# Optosense.net
KiCad netlist of a schematic drawn in Altium Designer
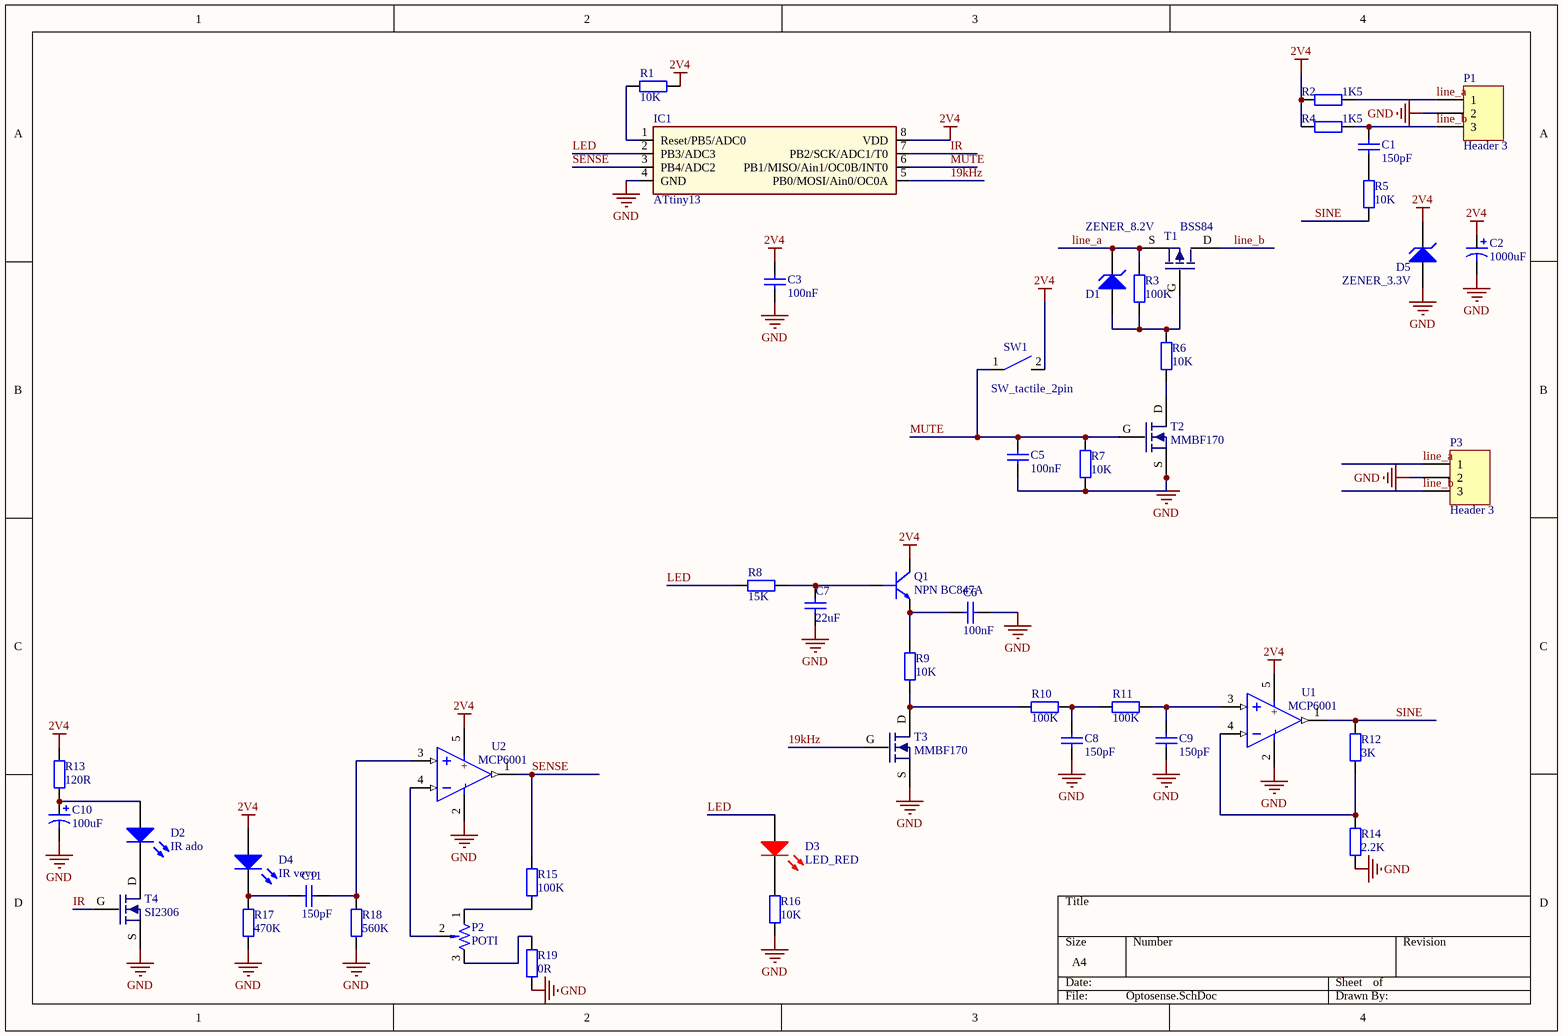
[diagram p0: Optosense.SchDoc]

(export (version "E")
  (design (tool "Eeschema 10.0.6"))
  (components
    (comp (ref "C1")
      (value "150pF")
      (footprint "FP_0603_CAP_080")
      (description "Capacitor")
      (libsource (lib "Capacitor") (part "CAP"))
    )
    (comp (ref "C2")
      (value "1000uF")
      (footprint "CAP_8x11_fekvo")
      (description "Polarized Capacitor")
      (libsource (lib "Capacitor") (part "CAP_ELECT"))
    )
    (comp (ref "C3")
      (value "100nF")
      (footprint "FP_0603_CAP_080")
      (description "Capacitor")
      (libsource (lib "Capacitor") (part "CAP"))
    )
    (comp (ref "C5")
      (value "100nF")
      (footprint "FP_0603_CAP_080")
      (description "Capacitor")
      (libsource (lib "Capacitor") (part "CAP"))
    )
    (comp (ref "C6")
      (value "100nF")
      (footprint "FP_0603_CAP_080")
      (description "Capacitor")
      (libsource (lib "Capacitor") (part "CAP"))
    )
    (comp (ref "C7")
      (value "22uF")
      (footprint "FP_1206_CAP_125")
      (description "Capacitor")
      (libsource (lib "Miscellaneous Devices") (part "Cap"))
    )
    (comp (ref "C8")
      (value "150pF")
      (footprint "FP_0603_CAP_080")
      (description "Capacitor")
      (libsource (lib "Capacitor") (part "CAP"))
    )
    (comp (ref "C9")
      (value "150pF")
      (footprint "FP_0603_CAP_080")
      (description "Capacitor")
      (libsource (lib "Capacitor") (part "CAP"))
    )
    (comp (ref "C10")
      (value "100uF")
      (footprint "FP_3528")
      (description "Polarized Capacitor")
      (libsource (lib "Capacitor") (part "CAP_ELECT"))
    )
    (comp (ref "C11")
      (value "150pF")
      (footprint "FP_0603_CAP_080")
      (description "Capacitor")
      (libsource (lib "Capacitor") (part "CAP"))
    )
    (comp (ref "D1")
      (value "ZENER_8.2V")
      (footprint "SOD-80")
      (description "Zener Diode")
      (libsource (lib "Diode") (part "ZENER"))
    )
    (comp (ref "D2")
      (value "IR ado")
      (footprint "LED_IR_5mm")
      (description "Typical LED")
      (libsource (lib "Led_optical") (part "LED_B"))
    )
    (comp (ref "D3")
      (value "LED_RED")
      (footprint "led_3mm_standing R")
      (description "Typical LED")
      (libsource (lib "Led_optical") (part "LED_R"))
    )
    (comp (ref "D4")
      (value "IR vevo")
      (footprint "LED_IR_5mm")
      (description "Typical LED")
      (libsource (lib "Led_optical") (part "LED_B"))
    )
    (comp (ref "D5")
      (value "ZENER_3.3V")
      (footprint "SOD-80")
      (description "Zener Diode")
      (libsource (lib "Diode") (part "ZENER"))
    )
    (comp (ref "IC1") (value "ATtiny13") (footprint "WSON_n_SOIC8") (libsource (lib "uC") (part "ATtiny13")))
    (comp (ref "P1")
      (value "Header 3")
      (footprint "HDR1X3")
      (description "Header, 3-Pin")
      (fields (field (name "PUBLISHER") "Altium Limited"))
      (libsource (lib "Miscellaneous Connectors") (part "Header 3"))
    )
    (comp (ref "P2")
      (value "POTI")
      (footprint "RES_trimmer_helipot_mini_90")
      (libsource (lib "Resistor") (part "POTI"))
    )
    (comp (ref "P3")
      (value "Header 3")
      (footprint "HDR1X3")
      (description "Header, 3-Pin")
      (fields (field (name "PUBLISHER") "Altium Limited"))
      (libsource (lib "Miscellaneous Connectors") (part "Header 3"))
    )
    (comp (ref "Q1") (value "NPN BC847A") (footprint "TR_SOT23") (libsource (lib "Transistor") (part "NPN")))
    (comp (ref "R1")
      (value "10K")
      (footprint "FP_0603_RES")
      (description "Resistor")
      (libsource (lib "") (part "RES_1"))
    )
    (comp (ref "R2")
      (value "1K5")
      (footprint "FP_0603_RES")
      (description "Resistor")
      (libsource (lib "") (part "RES_3"))
    )
    (comp (ref "R3")
      (value "100K")
      (footprint "FP_0603_RES")
      (description "Resistor")
      (libsource (lib "Resistor") (part "RES"))
    )
    (comp (ref "R4")
      (value "1K5")
      (footprint "FP_0603_RES")
      (description "Resistor")
      (libsource (lib "") (part "RES_3"))
    )
    (comp (ref "R5")
      (value "10K")
      (footprint "FP_0603_RES")
      (description "Resistor")
      (libsource (lib "") (part "RES_2"))
    )
    (comp (ref "R6")
      (value "10K")
      (footprint "FP_0603_RES")
      (description "Resistor")
      (libsource (lib "Resistor") (part "RES"))
    )
    (comp (ref "R7")
      (value "10K")
      (footprint "FP_0603_RES")
      (description "Resistor")
      (libsource (lib "Resistor") (part "RES"))
    )
    (comp (ref "R8")
      (value "15K")
      (footprint "FP_0603_RES")
      (description "Resistor")
      (libsource (lib "") (part "RES_1"))
    )
    (comp (ref "R9")
      (value "10K")
      (footprint "FP_0603_RES")
      (description "Resistor")
      (libsource (lib "Resistor") (part "RES"))
    )
    (comp (ref "R10")
      (value "100K")
      (footprint "FP_0603_RES")
      (description "Resistor")
      (libsource (lib "") (part "RES_1"))
    )
    (comp (ref "R11")
      (value "100K")
      (footprint "FP_0603_RES")
      (description "Resistor")
      (libsource (lib "") (part "RES_1"))
    )
    (comp (ref "R12")
      (value "3K")
      (footprint "FP_0603_RES")
      (description "Resistor")
      (libsource (lib "Resistor") (part "RES"))
    )
    (comp (ref "R13")
      (value "120R")
      (footprint "FP_0603_RES")
      (description "Resistor")
      (libsource (lib "") (part "RES_2"))
    )
    (comp (ref "R14")
      (value "2.2K")
      (footprint "FP_0603_RES")
      (description "Resistor")
      (libsource (lib "Resistor") (part "RES"))
    )
    (comp (ref "R15")
      (value "100K")
      (footprint "FP_0603_RES")
      (description "Resistor")
      (libsource (lib "") (part "RES_2"))
    )
    (comp (ref "R16")
      (value "10K")
      (footprint "FP_0603_RES")
      (description "Resistor")
      (libsource (lib "") (part "RES_2"))
    )
    (comp (ref "R17")
      (value "470K")
      (footprint "FP_0603_RES")
      (description "Resistor")
      (libsource (lib "") (part "RES_2"))
    )
    (comp (ref "R18")
      (value "560K")
      (footprint "FP_0603_RES")
      (description "Resistor")
      (libsource (lib "") (part "RES_2"))
    )
    (comp (ref "R19")
      (value "0R")
      (footprint "FP_0603_RES")
      (description "Resistor")
      (libsource (lib "") (part "RES_2"))
    )
    (comp (ref "SW1")
      (value "SW_tactile_2pin")
      (footprint "SW_TACT_2PIN")
      (libsource (lib "Switch") (part "SW_tactile_2pin"))
    )
    (comp (ref "T1") (value "BSS84") (footprint "FET_SOT23") (libsource (lib "FET") (part "PMOS")))
    (comp (ref "T2") (value "MMBF170") (footprint "FET_SOT23") (libsource (lib "FET") (part "NMOS")))
    (comp (ref "T3") (value "MMBF170") (footprint "FET_SOT23") (libsource (lib "FET") (part "NMOS")))
    (comp (ref "T4") (value "SI2306") (footprint "FET_SOT23") (libsource (lib "FET") (part "NMOS")))
    (comp (ref "U1")
      (value "MCP6001")
      (footprint "ANALOG_SOT23-5")
      (libsource (lib "Analog") (part "MCP6001"))
    )
    (comp (ref "U2")
      (value "MCP6001")
      (footprint "ANALOG_SOT23-5")
      (libsource (lib "Analog") (part "MCP6001"))
    )
  )
  (nets
    (net (code "1") (name "/19kHz") (class "Default")
      (node (ref "IC1") (pin "5") (pinfunction "PB0/MOSI/Ain0/OC0A_5") (pintype "passive"))
      (node (ref "T3") (pin "G") (pinfunction "G_G") (pintype "passive"))
    )
    (net (code "2") (name "/IR") (class "Default")
      (node (ref "IC1") (pin "7") (pinfunction "PB2/SCK/ADC1/T0_7") (pintype "passive"))
      (node (ref "T4") (pin "G") (pinfunction "G_G") (pintype "passive"))
    )
    (net (code "3") (name "/LED") (class "Default")
      (node (ref "D3") (pin "A") (pinfunction "A_A") (pintype "passive"))
      (node (ref "IC1") (pin "2") (pinfunction "PB3/ADC3_2") (pintype "passive"))
      (node (ref "R8") (pin "2") (pinfunction "2_2") (pintype "passive"))
    )
    (net (code "4") (name "/MUTE") (class "Default")
      (node (ref "C5") (pin "2") (pinfunction "2_2") (pintype "passive"))
      (node (ref "IC1") (pin "6") (pinfunction "PB1/MISO/Ain1/OC0B/INT0_6") (pintype "passive"))
      (node (ref "R7") (pin "1") (pinfunction "1_1") (pintype "passive"))
      (node (ref "SW1") (pin "1") (pinfunction "1_1") (pintype "passive"))
      (node (ref "T2") (pin "G") (pinfunction "G_G") (pintype "passive"))
    )
    (net (code "5") (name "/SENSE") (class "Default")
      (node (ref "IC1") (pin "3") (pinfunction "PB4/ADC2_3") (pintype "passive"))
      (node (ref "R15") (pin "2") (pinfunction "2_2") (pintype "passive"))
      (node (ref "U2") (pin "1") (pinfunction "OUT1_1") (pintype "output"))
    )
    (net (code "6") (name "/SINE") (class "Default")
      (node (ref "R12") (pin "1") (pinfunction "1_1") (pintype "passive"))
      (node (ref "R5") (pin "1") (pinfunction "1_1") (pintype "passive"))
      (node (ref "U1") (pin "1") (pinfunction "OUT1_1") (pintype "output"))
    )
    (net (code "7") (name "/line_a") (class "Default")
      (node (ref "D1") (pin "K") (pinfunction "K_K") (pintype "passive"))
      (node (ref "P1") (pin "1") (pinfunction "1_1") (pintype "passive"))
      (node (ref "P3") (pin "1") (pinfunction "1_1") (pintype "passive"))
      (node (ref "R2") (pin "2") (pinfunction "2_2") (pintype "passive"))
      (node (ref "R3") (pin "1") (pinfunction "1_1") (pintype "passive"))
      (node (ref "T1") (pin "S") (pinfunction "S_S") (pintype "passive"))
    )
    (net (code "8") (name "/line_b") (class "Default")
      (node (ref "C1") (pin "2") (pinfunction "2_2") (pintype "passive"))
      (node (ref "P1") (pin "3") (pinfunction "3_3") (pintype "passive"))
      (node (ref "P3") (pin "3") (pinfunction "3_3") (pintype "passive"))
      (node (ref "R4") (pin "2") (pinfunction "2_2") (pintype "passive"))
      (node (ref "T1") (pin "D") (pinfunction "D_D") (pintype "passive"))
    )
    (net (code "9") (name "2V4") (class "Default")
      (node (ref "C2") (pin "P") (pintype "passive"))
      (node (ref "C3") (pin "2") (pinfunction "2_2") (pintype "passive"))
      (node (ref "D4") (pin "A") (pinfunction "A_A") (pintype "passive"))
      (node (ref "D5") (pin "K") (pinfunction "K_K") (pintype "passive"))
      (node (ref "IC1") (pin "8") (pinfunction "VDD_8") (pintype "passive"))
      (node (ref "Q1") (pin "C") (pinfunction "C_C") (pintype "passive"))
      (node (ref "R1") (pin "1") (pinfunction "1_1") (pintype "passive"))
      (node (ref "R13") (pin "2") (pinfunction "2_2") (pintype "passive"))
      (node (ref "R2") (pin "1") (pinfunction "1_1") (pintype "passive"))
      (node (ref "R4") (pin "1") (pinfunction "1_1") (pintype "passive"))
      (node (ref "SW1") (pin "2") (pinfunction "2_2") (pintype "passive"))
      (node (ref "U1") (pin "5") (pinfunction "+_5") (pintype "power_in"))
      (node (ref "U2") (pin "5") (pinfunction "+_5") (pintype "power_in"))
    )
    (net (code "10") (name "GND") (class "Default")
      (node (ref "C10") (pin "N") (pintype "passive"))
      (node (ref "C2") (pin "N") (pintype "passive"))
      (node (ref "C3") (pin "1") (pinfunction "1_1") (pintype "passive"))
      (node (ref "C5") (pin "1") (pinfunction "1_1") (pintype "passive"))
      (node (ref "C6") (pin "1") (pinfunction "1_1") (pintype "passive"))
      (node (ref "C7") (pin "1") (pinfunction "1_1") (pintype "passive"))
      (node (ref "C8") (pin "1") (pinfunction "1_1") (pintype "passive"))
      (node (ref "C9") (pin "1") (pinfunction "1_1") (pintype "passive"))
      (node (ref "D5") (pin "A") (pinfunction "A_A") (pintype "passive"))
      (node (ref "IC1") (pin "4") (pinfunction "GND_4") (pintype "passive"))
      (node (ref "P1") (pin "2") (pinfunction "2_2") (pintype "passive"))
      (node (ref "P3") (pin "2") (pinfunction "2_2") (pintype "passive"))
      (node (ref "R14") (pin "2") (pinfunction "2_2") (pintype "passive"))
      (node (ref "R16") (pin "1") (pinfunction "1_1") (pintype "passive"))
      (node (ref "R17") (pin "1") (pinfunction "1_1") (pintype "passive"))
      (node (ref "R18") (pin "1") (pinfunction "1_1") (pintype "passive"))
      (node (ref "R19") (pin "1") (pinfunction "1_1") (pintype "passive"))
      (node (ref "R7") (pin "2") (pinfunction "2_2") (pintype "passive"))
      (node (ref "T2") (pin "S") (pinfunction "S_S") (pintype "passive"))
      (node (ref "T3") (pin "S") (pinfunction "S_S") (pintype "passive"))
      (node (ref "T4") (pin "S") (pinfunction "S_S") (pintype "passive"))
      (node (ref "U1") (pin "2") (pinfunction "-_2") (pintype "power_in"))
      (node (ref "U2") (pin "2") (pinfunction "-_2") (pintype "power_in"))
    )
    (net (code "11") (name "Net-(C1-Pad1)") (class "Default")
      (node (ref "C1") (pin "1") (pinfunction "1_1") (pintype "passive"))
      (node (ref "R5") (pin "2") (pinfunction "2_2") (pintype "passive"))
    )
    (net (code "12") (name "Net-(C6-Pad2)") (class "Default")
      (node (ref "C6") (pin "2") (pinfunction "2_2") (pintype "passive"))
      (node (ref "Q1") (pin "E") (pinfunction "E_E") (pintype "passive"))
      (node (ref "R9") (pin "1") (pinfunction "1_1") (pintype "passive"))
    )
    (net (code "13") (name "Net-(C7-Pad2)") (class "Default")
      (node (ref "C7") (pin "2") (pinfunction "2_2") (pintype "passive"))
      (node (ref "Q1") (pin "B") (pinfunction "B_B") (pintype "passive"))
      (node (ref "R8") (pin "1") (pinfunction "1_1") (pintype "passive"))
    )
    (net (code "14") (name "Net-(C8-Pad2)") (class "Default")
      (node (ref "C8") (pin "2") (pinfunction "2_2") (pintype "passive"))
      (node (ref "R10") (pin "1") (pinfunction "1_1") (pintype "passive"))
      (node (ref "R11") (pin "2") (pinfunction "2_2") (pintype "passive"))
    )
    (net (code "15") (name "Net-(C10-PadP)") (class "Default")
      (node (ref "C10") (pin "P") (pintype "passive"))
      (node (ref "D2") (pin "A") (pinfunction "A_A") (pintype "passive"))
      (node (ref "R13") (pin "1") (pinfunction "1_1") (pintype "passive"))
    )
    (net (code "16") (name "Net-(C11-Pad1)") (class "Default")
      (node (ref "C11") (pin "1") (pinfunction "1_1") (pintype "passive"))
      (node (ref "D4") (pin "K") (pinfunction "K_K") (pintype "passive"))
      (node (ref "R17") (pin "2") (pinfunction "2_2") (pintype "passive"))
    )
    (net (code "17") (name "Net-(D1-PadA)") (class "Default")
      (node (ref "D1") (pin "A") (pinfunction "A_A") (pintype "passive"))
      (node (ref "R3") (pin "2") (pinfunction "2_2") (pintype "passive"))
      (node (ref "R6") (pin "1") (pinfunction "1_1") (pintype "passive"))
      (node (ref "T1") (pin "G") (pinfunction "G_G") (pintype "passive"))
    )
    (net (code "18") (name "Net-(D2-PadK)") (class "Default")
      (node (ref "D2") (pin "K") (pinfunction "K_K") (pintype "passive"))
      (node (ref "T4") (pin "D") (pinfunction "D_D") (pintype "passive"))
    )
    (net (code "19") (name "Net-(D3-PadK)") (class "Default")
      (node (ref "D3") (pin "K") (pinfunction "K_K") (pintype "passive"))
      (node (ref "R16") (pin "2") (pinfunction "2_2") (pintype "passive"))
    )
    (net (code "20") (name "Net-(IC1-Reset{slash}PB5{slash}ADC0)") (class "Default")
      (node (ref "IC1") (pin "1") (pinfunction "Reset/PB5/ADC0_1") (pintype "passive"))
      (node (ref "R1") (pin "2") (pinfunction "2_2") (pintype "passive"))
    )
    (net (code "21") (name "Net-(P2-2)") (class "Default")
      (node (ref "P2") (pin "3") (pinfunction "2_3") (pintype "passive"))
      (node (ref "R19") (pin "2") (pinfunction "2_2") (pintype "passive"))
    )
    (net (code "22") (name "Net-(P2-Pad1)") (class "Default")
      (node (ref "P2") (pin "1") (pinfunction "1_1") (pintype "passive"))
      (node (ref "R15") (pin "1") (pinfunction "1_1") (pintype "passive"))
    )
    (net (code "23") (name "Net-(P2-t)") (class "Default")
      (node (ref "P2") (pin "2") (pinfunction "t_2") (pintype "passive"))
      (node (ref "U2") (pin "4") (pinfunction "IN1-_4") (pintype "input"))
    )
    (net (code "24") (name "Net-(R6-Pad2)") (class "Default")
      (node (ref "R6") (pin "2") (pinfunction "2_2") (pintype "passive"))
      (node (ref "T2") (pin "D") (pinfunction "D_D") (pintype "passive"))
    )
    (net (code "25") (name "Net-(R10-Pad2)") (class "Default")
      (node (ref "R10") (pin "2") (pinfunction "2_2") (pintype "passive"))
      (node (ref "R9") (pin "2") (pinfunction "2_2") (pintype "passive"))
      (node (ref "T3") (pin "D") (pinfunction "D_D") (pintype "passive"))
    )
    (net (code "26") (name "Net-(U1-IN1+)") (class "Default")
      (node (ref "C9") (pin "2") (pinfunction "2_2") (pintype "passive"))
      (node (ref "R11") (pin "1") (pinfunction "1_1") (pintype "passive"))
      (node (ref "U1") (pin "3") (pinfunction "IN1+_3") (pintype "input"))
    )
    (net (code "27") (name "Net-(U1-IN1-)") (class "Default")
      (node (ref "R12") (pin "2") (pinfunction "2_2") (pintype "passive"))
      (node (ref "R14") (pin "1") (pinfunction "1_1") (pintype "passive"))
      (node (ref "U1") (pin "4") (pinfunction "IN1-_4") (pintype "input"))
    )
    (net (code "28") (name "Net-(U2-IN1+)") (class "Default")
      (node (ref "C11") (pin "2") (pinfunction "2_2") (pintype "passive"))
      (node (ref "R18") (pin "2") (pinfunction "2_2") (pintype "passive"))
      (node (ref "U2") (pin "3") (pinfunction "IN1+_3") (pintype "input"))
    )
  )
)
